# Sheet1.net
KiCad netlist of a schematic drawn in Altium Designer
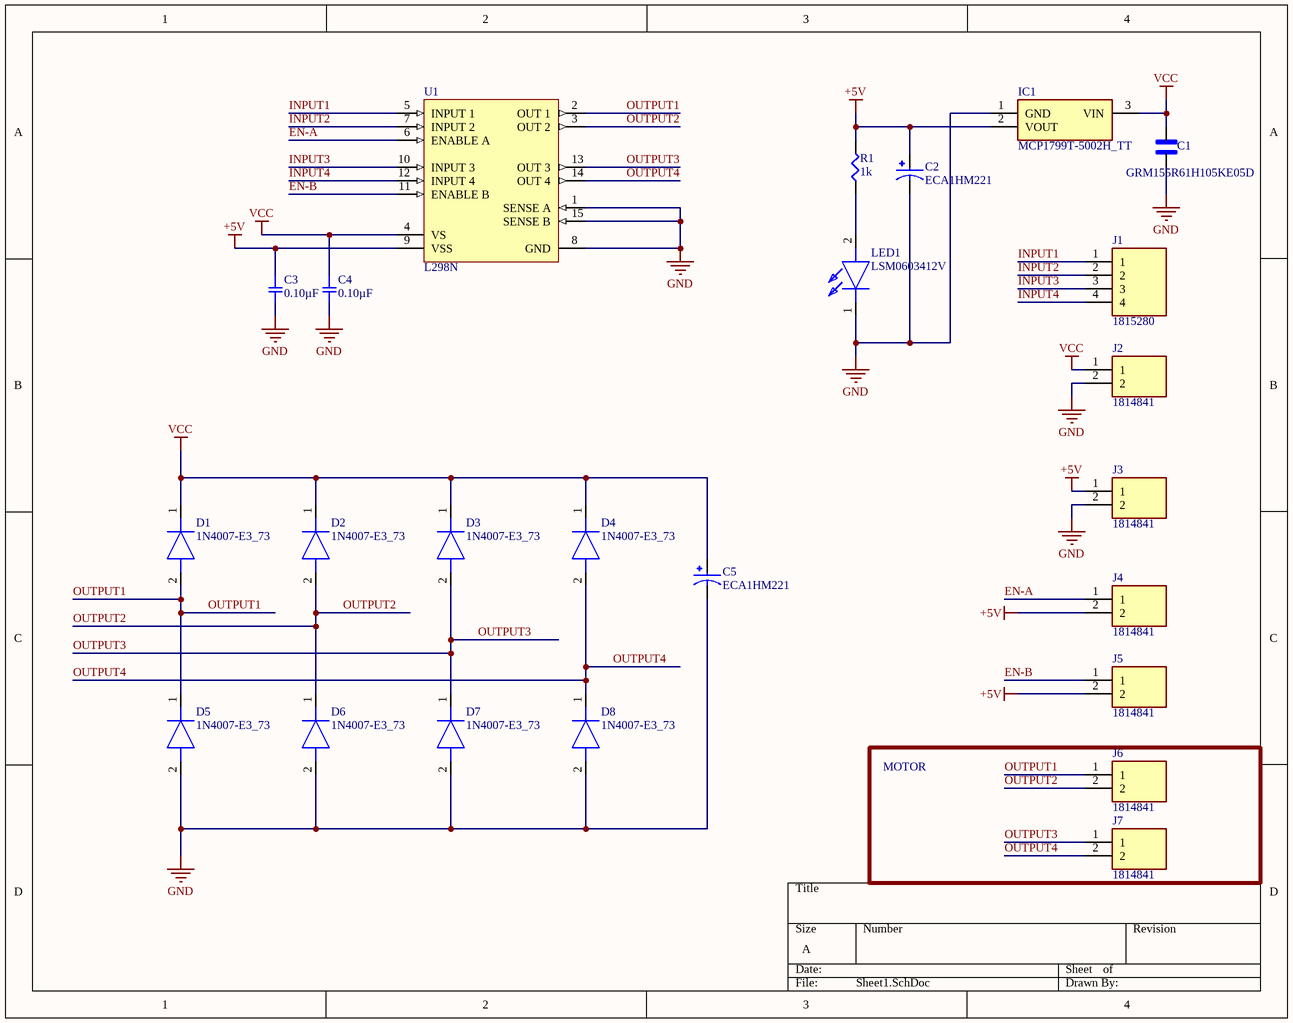
[diagram p0: Sheet1.SchDoc]

(export (version "E")
  (design (tool "Eeschema 10.0.6"))
  (components
    (comp (ref "C1")
      (value "GRM155R61H105KE05D")
      (footprint "GRM155R61H105KE05D:CAPC1005X60N")
      (description "Capacitor Ceramic Multilayer (MLCC)")
      (fields (field (name "MF") "{'manufacturer': u'Murata'}"))
      (libsource (lib "*") (part "GRM155R61H105KE05D"))
    )
    (comp (ref "C2")
      (value "ECA1HM221")
      (footprint "ECA-1HM221:CAPPRD500W60D1000H1250")
      (description "M-A")
      (fields (field (name "MF") "{'manufacturer': u'Panasonic'}"))
      (libsource (lib "*") (part "ECA1HM221"))
    )
    (comp (ref "C3")
      (value "0.10µF")
      (footprint "SMD-0402C")
      (description "CAP CER 0.1UF 50V X5R 0402")
      (fields
        (field (name "DIGI-KEY PART NUMBER") "490-10697-1-ND")
        (field (name "PART NUMBER") "GRM155R61H104KE14D")
      )
      (libsource (lib "capacitor_murata_0402") (part "GRM155R61H104KE14D"))
    )
    (comp (ref "C4")
      (value "0.10µF")
      (footprint "SMD-0402C")
      (description "CAP CER 0.1UF 50V X5R 0402")
      (fields
        (field (name "DIGI-KEY PART NUMBER") "490-10697-1-ND")
        (field (name "PART NUMBER") "GRM155R61H104KE14D")
      )
      (libsource (lib "capacitor_murata_0402") (part "GRM155R61H104KE14D"))
    )
    (comp (ref "C5")
      (value "ECA1HM221")
      (footprint "ECA-1HM221:CAPPRD500W60D1000H1250")
      (description "M-A")
      (fields (field (name "MF") "{'manufacturer': u'Panasonic'}"))
      (libsource (lib "*") (part "ECA1HM221"))
    )
    (comp (ref "D1")
      (value "1N4007-E3_73")
      (footprint "PCBComponent_1")
      (description "Diode")
      (fields
        (field (name "MANUFACTURER_PART_NUMBER") "1N4007-E3/73")
        (field (name "MOUSER PART NUMBER") "625-1N4007-E3/73")
      )
      (libsource (lib "SamacSys") (part "1N4007-E3_73"))
    )
    (comp (ref "D2")
      (value "1N4007-E3_73")
      (footprint "PCBComponent_1")
      (description "Diode")
      (fields
        (field (name "MANUFACTURER_PART_NUMBER") "1N4007-E3/73")
        (field (name "MOUSER PART NUMBER") "625-1N4007-E3/73")
      )
      (libsource (lib "SamacSys") (part "1N4007-E3_73"))
    )
    (comp (ref "D3")
      (value "1N4007-E3_73")
      (footprint "PCBComponent_1")
      (description "Diode")
      (fields
        (field (name "MANUFACTURER_PART_NUMBER") "1N4007-E3/73")
        (field (name "MOUSER PART NUMBER") "625-1N4007-E3/73")
      )
      (libsource (lib "SamacSys") (part "1N4007-E3_73"))
    )
    (comp (ref "D4")
      (value "1N4007-E3_73")
      (footprint "PCBComponent_1")
      (description "Diode")
      (fields
        (field (name "MANUFACTURER_PART_NUMBER") "1N4007-E3/73")
        (field (name "MOUSER PART NUMBER") "625-1N4007-E3/73")
      )
      (libsource (lib "SamacSys") (part "1N4007-E3_73"))
    )
    (comp (ref "D5")
      (value "1N4007-E3_73")
      (footprint "PCBComponent_1")
      (description "Diode")
      (fields
        (field (name "MANUFACTURER_PART_NUMBER") "1N4007-E3/73")
        (field (name "MOUSER PART NUMBER") "625-1N4007-E3/73")
      )
      (libsource (lib "SamacSys") (part "1N4007-E3_73"))
    )
    (comp (ref "D6")
      (value "1N4007-E3_73")
      (footprint "PCBComponent_1")
      (description "Diode")
      (fields
        (field (name "MANUFACTURER_PART_NUMBER") "1N4007-E3/73")
        (field (name "MOUSER PART NUMBER") "625-1N4007-E3/73")
      )
      (libsource (lib "SamacSys") (part "1N4007-E3_73"))
    )
    (comp (ref "D7")
      (value "1N4007-E3_73")
      (footprint "PCBComponent_1")
      (description "Diode")
      (fields
        (field (name "MANUFACTURER_PART_NUMBER") "1N4007-E3/73")
        (field (name "MOUSER PART NUMBER") "625-1N4007-E3/73")
      )
      (libsource (lib "SamacSys") (part "1N4007-E3_73"))
    )
    (comp (ref "D8")
      (value "1N4007-E3_73")
      (footprint "PCBComponent_1")
      (description "Diode")
      (fields
        (field (name "MANUFACTURER_PART_NUMBER") "1N4007-E3/73")
        (field (name "MOUSER PART NUMBER") "625-1N4007-E3/73")
      )
      (libsource (lib "SamacSys") (part "1N4007-E3_73"))
    )
    (comp (ref "IC1")
      (value "MCP1799T-5002H_TT")
      (footprint "SamacSys:SOT95P237X112-3N")
      (description "Integrated Circuit")
      (fields
        (field (name "MANUFACTURER_PART_NUMBER") "MCP1799T-5002H/TT")
        (field (name "MOUSER PART NUMBER") "579-CP1799T-5002H/TT")
      )
      (libsource (lib "*") (part "MCP1799T-5002H_TT"))
    )
    (comp (ref "J1")
      (value "1815280")
      (footprint "SamacSys:1815280")
      (description "Connector")
      (fields (field (name "MOUSER PART NUMBER") "651-1815280"))
      (libsource (lib "SamacSys") (part "1815280"))
    )
    (comp (ref "J2")
      (value "1814841")
      (footprint "SamacSys:1814841")
      (description "Connector")
      (fields (field (name "MOUSER PART NUMBER") "651-1814841"))
      (libsource (lib "SamacSys") (part "1814841"))
    )
    (comp (ref "J3")
      (value "1814841")
      (footprint "SamacSys:1814841")
      (description "Connector")
      (fields (field (name "MOUSER PART NUMBER") "651-1814841"))
      (libsource (lib "SamacSys") (part "1814841"))
    )
    (comp (ref "J4")
      (value "1814841")
      (footprint "SamacSys:1814841")
      (description "Connector")
      (fields (field (name "MOUSER PART NUMBER") "651-1814841"))
      (libsource (lib "SamacSys") (part "1814841"))
    )
    (comp (ref "J5")
      (value "1814841")
      (footprint "SamacSys:1814841")
      (description "Connector")
      (fields (field (name "MOUSER PART NUMBER") "651-1814841"))
      (libsource (lib "SamacSys") (part "1814841"))
    )
    (comp (ref "J6")
      (value "1814841")
      (footprint "SamacSys:1814841")
      (description "Connector")
      (fields (field (name "MOUSER PART NUMBER") "651-1814841"))
      (libsource (lib "SamacSys") (part "1814841"))
    )
    (comp (ref "J7")
      (value "1814841")
      (footprint "SamacSys:1814841")
      (description "Connector")
      (fields (field (name "MOUSER PART NUMBER") "651-1814841"))
      (libsource (lib "SamacSys") (part "1814841"))
    )
    (comp (ref "LED1")
      (value "LSM0603412V")
      (footprint "SamacSys:LSM0603412V")
      (description "LED")
      (fields (field (name "MOUSER PART NUMBER") "593-LSM0603412V"))
      (libsource (lib "SamacSys") (part "LSM0603412V"))
    )
    (comp (ref "R1")
      (value "1k")
      (footprint "SMD-0402-RES")
      (description "RES SMD 1K OHM 5% 1/10W 0402")
      (fields (field (name "PART NUMBER") "ERJ-2GEJ102X") (field (name "DIGI-KEY PART NUMBER") "P1.0KJCT-ND"))
      (libsource (lib "Panasonic_ERJ_0402") (part "ERJ-2GEJ102X"))
    )
    (comp (ref "U1")
      (value "L298N")
      (footprint "STM-FM-15")
      (description "Dual Full-Bridge Driver, 4.8 to 46 V, -40 to 150 degC, 15-Pin FM (MW 15L), RoHS, Tube")
      (fields (field (name "MANUFACTURER") "STMicroelectronics") (field (name "PARTNUMBER") "L298"))
      (libsource (lib "Altium Content Vault") (part "STM-L298-15"))
    )
  )
  (nets
    (net (code "1") (name "+5V") (class "Default")
      (node (ref "C2") (pin "P") (pinfunction "P_P") (pintype "passive"))
      (node (ref "C3") (pin "1") (pinfunction "1_1") (pintype "passive"))
      (node (ref "IC1") (pin "2") (pinfunction "VOUT_2") (pintype "passive"))
      (node (ref "J3") (pin "1") (pinfunction "1_1") (pintype "passive"))
      (node (ref "J4") (pin "2") (pinfunction "2_2") (pintype "passive"))
      (node (ref "J5") (pin "2") (pinfunction "2_2") (pintype "passive"))
      (node (ref "R1") (pin "2") (pinfunction "2_2") (pintype "passive"))
      (node (ref "U1") (pin "9") (pinfunction "VSS_9") (pintype "power_in"))
    )
    (net (code "2") (name "/EN-A") (class "Default")
      (node (ref "J4") (pin "1") (pinfunction "1_1") (pintype "passive"))
      (node (ref "U1") (pin "6") (pinfunction "ENABLE_A_6") (pintype "input"))
    )
    (net (code "3") (name "/EN-B") (class "Default")
      (node (ref "J5") (pin "1") (pinfunction "1_1") (pintype "passive"))
      (node (ref "U1") (pin "11") (pinfunction "ENABLE_B_11") (pintype "input"))
    )
    (net (code "4") (name "/INPUT1") (class "Default")
      (node (ref "J1") (pin "1") (pinfunction "1_1") (pintype "passive"))
      (node (ref "U1") (pin "5") (pinfunction "INPUT_1_5") (pintype "input"))
    )
    (net (code "5") (name "/INPUT2") (class "Default")
      (node (ref "J1") (pin "2") (pinfunction "2_2") (pintype "passive"))
      (node (ref "U1") (pin "7") (pinfunction "INPUT_2_7") (pintype "input"))
    )
    (net (code "6") (name "/INPUT3") (class "Default")
      (node (ref "J1") (pin "3") (pinfunction "3_3") (pintype "passive"))
      (node (ref "U1") (pin "10") (pinfunction "INPUT_3_10") (pintype "input"))
    )
    (net (code "7") (name "/INPUT4") (class "Default")
      (node (ref "J1") (pin "4") (pinfunction "4_4") (pintype "passive"))
      (node (ref "U1") (pin "12") (pinfunction "INPUT_4_12") (pintype "input"))
    )
    (net (code "8") (name "/OUTPUT1") (class "Default")
      (node (ref "D1") (pin "2") (pinfunction "A_2") (pintype "passive"))
      (node (ref "D5") (pin "1") (pinfunction "K_1") (pintype "passive"))
      (node (ref "J6") (pin "1") (pinfunction "1_1") (pintype "passive"))
      (node (ref "U1") (pin "2") (pinfunction "OUT_1_2") (pintype "output"))
    )
    (net (code "9") (name "/OUTPUT2") (class "Default")
      (node (ref "D2") (pin "2") (pinfunction "A_2") (pintype "passive"))
      (node (ref "D6") (pin "1") (pinfunction "K_1") (pintype "passive"))
      (node (ref "J6") (pin "2") (pinfunction "2_2") (pintype "passive"))
      (node (ref "U1") (pin "3") (pinfunction "OUT_2_3") (pintype "output"))
    )
    (net (code "10") (name "/OUTPUT3") (class "Default")
      (node (ref "D3") (pin "2") (pinfunction "A_2") (pintype "passive"))
      (node (ref "D7") (pin "1") (pinfunction "K_1") (pintype "passive"))
      (node (ref "J7") (pin "1") (pinfunction "1_1") (pintype "passive"))
      (node (ref "U1") (pin "13") (pinfunction "OUT_3_13") (pintype "output"))
    )
    (net (code "11") (name "/OUTPUT4") (class "Default")
      (node (ref "D4") (pin "2") (pinfunction "A_2") (pintype "passive"))
      (node (ref "D8") (pin "1") (pinfunction "K_1") (pintype "passive"))
      (node (ref "J7") (pin "2") (pinfunction "2_2") (pintype "passive"))
      (node (ref "U1") (pin "14") (pinfunction "OUT_4_14") (pintype "output"))
    )
    (net (code "12") (name "GND") (class "Default")
      (node (ref "C1") (pin "1") (pinfunction "1_1") (pintype "passive"))
      (node (ref "C2") (pin "N") (pinfunction "N_N") (pintype "passive"))
      (node (ref "C3") (pin "2") (pinfunction "2_2") (pintype "passive"))
      (node (ref "C4") (pin "2") (pinfunction "2_2") (pintype "passive"))
      (node (ref "C5") (pin "N") (pinfunction "N_N") (pintype "passive"))
      (node (ref "D5") (pin "2") (pinfunction "A_2") (pintype "passive"))
      (node (ref "D6") (pin "2") (pinfunction "A_2") (pintype "passive"))
      (node (ref "D7") (pin "2") (pinfunction "A_2") (pintype "passive"))
      (node (ref "D8") (pin "2") (pinfunction "A_2") (pintype "passive"))
      (node (ref "IC1") (pin "1") (pinfunction "GND_1") (pintype "passive"))
      (node (ref "J2") (pin "2") (pinfunction "2_2") (pintype "passive"))
      (node (ref "J3") (pin "2") (pinfunction "2_2") (pintype "passive"))
      (node (ref "LED1") (pin "1") (pinfunction "K_1") (pintype "passive"))
      (node (ref "U1") (pin "1") (pinfunction "SENSE_A_1") (pintype "input"))
      (node (ref "U1") (pin "15") (pinfunction "SENSE_B_15") (pintype "input"))
      (node (ref "U1") (pin "8") (pinfunction "GND_8") (pintype "power_in"))
    )
    (net (code "13") (name "Net-(LED1-A)") (class "Default")
      (node (ref "LED1") (pin "2") (pinfunction "A_2") (pintype "passive"))
      (node (ref "R1") (pin "1") (pinfunction "1_1") (pintype "passive"))
    )
    (net (code "14") (name "VCC") (class "Default")
      (node (ref "C1") (pin "2") (pinfunction "2_2") (pintype "passive"))
      (node (ref "C4") (pin "1") (pinfunction "1_1") (pintype "passive"))
      (node (ref "C5") (pin "P") (pinfunction "P_P") (pintype "passive"))
      (node (ref "D1") (pin "1") (pinfunction "K_1") (pintype "passive"))
      (node (ref "D2") (pin "1") (pinfunction "K_1") (pintype "passive"))
      (node (ref "D3") (pin "1") (pinfunction "K_1") (pintype "passive"))
      (node (ref "D4") (pin "1") (pinfunction "K_1") (pintype "passive"))
      (node (ref "IC1") (pin "3") (pinfunction "VIN_3") (pintype "passive"))
      (node (ref "J2") (pin "1") (pinfunction "1_1") (pintype "passive"))
      (node (ref "U1") (pin "4") (pinfunction "VS_4") (pintype "power_in"))
    )
  )
)
